# expansion_gpio.net
KiCad netlist of a schematic drawn in Altium Designer
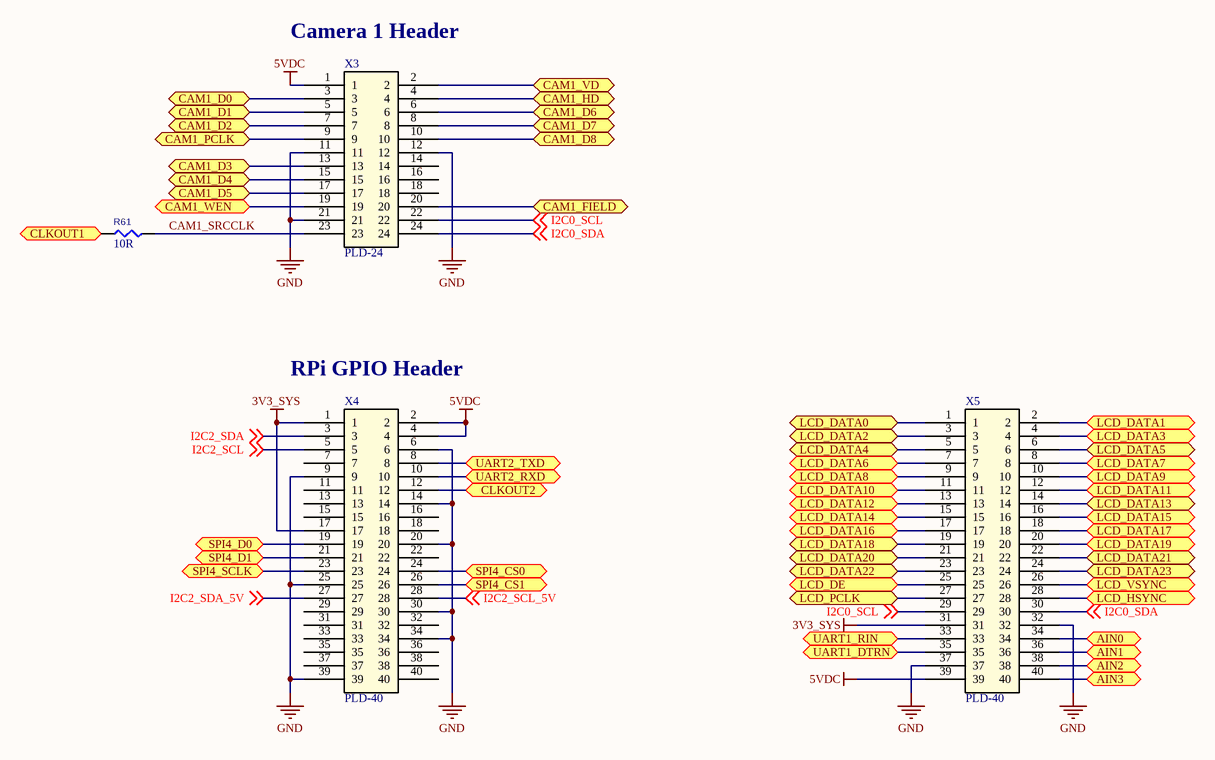
[diagram p0: expansion_gpio.SchDoc]

(export (version "E")
  (design (tool "Eeschema 10.0.6"))
  (components
    (comp (ref "R61")
      (value "10R")
      (footprint "RESC1608X55N")
      (description "R0603")
      (libsource (lib "spider") (part "R0603"))
    )
    (comp (ref "X3") (value "PLD-24") (footprint "PLD-24") (libsource (lib "spider") (part "HDR12x2")))
    (comp (ref "X4") (value "PLD-40") (footprint "PLD-40") (libsource (lib "spider") (part "HDR20x2")))
    (comp (ref "X5") (value "PLD-40") (footprint "PLD-40") (libsource (lib "spider") (part "HDR20x2")))
  )
  (nets
    (net (code "1") (name "/AIN0") (class "Default")
      (node (ref "X5") (pin "34") (pinfunction "34_34") (pintype "passive"))
    )
    (net (code "2") (name "/AIN1") (class "Default")
      (node (ref "X5") (pin "36") (pinfunction "36_36") (pintype "passive"))
    )
    (net (code "3") (name "/AIN2") (class "Default")
      (node (ref "X5") (pin "38") (pinfunction "38_38") (pintype "passive"))
    )
    (net (code "4") (name "/AIN3") (class "Default")
      (node (ref "X5") (pin "40") (pinfunction "40_40") (pintype "passive"))
    )
    (net (code "5") (name "/CAM1_D0") (class "Default")
      (node (ref "X3") (pin "3") (pinfunction "3_3") (pintype "passive"))
    )
    (net (code "6") (name "/CAM1_D1") (class "Default")
      (node (ref "X3") (pin "5") (pinfunction "5_5") (pintype "passive"))
    )
    (net (code "7") (name "/CAM1_D2") (class "Default")
      (node (ref "X3") (pin "7") (pinfunction "7_7") (pintype "passive"))
    )
    (net (code "8") (name "/CAM1_D3") (class "Default")
      (node (ref "X3") (pin "13") (pinfunction "13_13") (pintype "passive"))
    )
    (net (code "9") (name "/CAM1_D4") (class "Default")
      (node (ref "X3") (pin "15") (pinfunction "15_15") (pintype "passive"))
    )
    (net (code "10") (name "/CAM1_D5") (class "Default")
      (node (ref "X3") (pin "17") (pinfunction "17_17") (pintype "passive"))
    )
    (net (code "11") (name "/CAM1_D6") (class "Default")
      (node (ref "X3") (pin "6") (pinfunction "6_6") (pintype "passive"))
    )
    (net (code "12") (name "/CAM1_D7") (class "Default")
      (node (ref "X3") (pin "8") (pinfunction "8_8") (pintype "passive"))
    )
    (net (code "13") (name "/CAM1_D8") (class "Default")
      (node (ref "X3") (pin "10") (pinfunction "10_10") (pintype "passive"))
    )
    (net (code "14") (name "/CAM1_FIELD") (class "Default")
      (node (ref "X3") (pin "20") (pinfunction "20_20") (pintype "passive"))
    )
    (net (code "15") (name "/CAM1_HD") (class "Default")
      (node (ref "X3") (pin "4") (pinfunction "4_4") (pintype "passive"))
    )
    (net (code "16") (name "/CAM1_PCLK") (class "Default")
      (node (ref "X3") (pin "9") (pinfunction "9_9") (pintype "passive"))
    )
    (net (code "17") (name "/CAM1_SRCCLK") (class "Default")
      (node (ref "R61") (pin "2") (pinfunction "2_2") (pintype "passive"))
      (node (ref "X3") (pin "23") (pinfunction "23_23") (pintype "passive"))
    )
    (net (code "18") (name "/CAM1_VD") (class "Default")
      (node (ref "X3") (pin "2") (pinfunction "2_2") (pintype "passive"))
    )
    (net (code "19") (name "/CAM1_WEN") (class "Default")
      (node (ref "X3") (pin "19") (pinfunction "19_19") (pintype "passive"))
    )
    (net (code "20") (name "/CLKOUT1") (class "Default")
      (node (ref "R61") (pin "1") (pinfunction "1_1") (pintype "passive"))
    )
    (net (code "21") (name "/CLKOUT2") (class "Default")
      (node (ref "X4") (pin "12") (pinfunction "12_12") (pintype "passive"))
    )
    (net (code "22") (name "/LCD_DATA0") (class "Default")
      (node (ref "X5") (pin "1") (pinfunction "1_1") (pintype "passive"))
    )
    (net (code "23") (name "/LCD_DATA1") (class "Default")
      (node (ref "X5") (pin "2") (pinfunction "2_2") (pintype "passive"))
    )
    (net (code "24") (name "/LCD_DATA2") (class "Default")
      (node (ref "X5") (pin "3") (pinfunction "3_3") (pintype "passive"))
    )
    (net (code "25") (name "/LCD_DATA3") (class "Default")
      (node (ref "X5") (pin "4") (pinfunction "4_4") (pintype "passive"))
    )
    (net (code "26") (name "/LCD_DATA4") (class "Default")
      (node (ref "X5") (pin "5") (pinfunction "5_5") (pintype "passive"))
    )
    (net (code "27") (name "/LCD_DATA5") (class "Default")
      (node (ref "X5") (pin "6") (pinfunction "6_6") (pintype "passive"))
    )
    (net (code "28") (name "/LCD_DATA6") (class "Default")
      (node (ref "X5") (pin "7") (pinfunction "7_7") (pintype "passive"))
    )
    (net (code "29") (name "/LCD_DATA7") (class "Default")
      (node (ref "X5") (pin "8") (pinfunction "8_8") (pintype "passive"))
    )
    (net (code "30") (name "/LCD_DATA8") (class "Default")
      (node (ref "X5") (pin "9") (pinfunction "9_9") (pintype "passive"))
    )
    (net (code "31") (name "/LCD_DATA9") (class "Default")
      (node (ref "X5") (pin "10") (pinfunction "10_10") (pintype "passive"))
    )
    (net (code "32") (name "/LCD_DATA10") (class "Default")
      (node (ref "X5") (pin "11") (pinfunction "11_11") (pintype "passive"))
    )
    (net (code "33") (name "/LCD_DATA11") (class "Default")
      (node (ref "X5") (pin "12") (pinfunction "12_12") (pintype "passive"))
    )
    (net (code "34") (name "/LCD_DATA12") (class "Default")
      (node (ref "X5") (pin "13") (pinfunction "13_13") (pintype "passive"))
    )
    (net (code "35") (name "/LCD_DATA13") (class "Default")
      (node (ref "X5") (pin "14") (pinfunction "14_14") (pintype "passive"))
    )
    (net (code "36") (name "/LCD_DATA14") (class "Default")
      (node (ref "X5") (pin "15") (pinfunction "15_15") (pintype "passive"))
    )
    (net (code "37") (name "/LCD_DATA15") (class "Default")
      (node (ref "X5") (pin "16") (pinfunction "16_16") (pintype "passive"))
    )
    (net (code "38") (name "/LCD_DATA16") (class "Default")
      (node (ref "X5") (pin "17") (pinfunction "17_17") (pintype "passive"))
    )
    (net (code "39") (name "/LCD_DATA17") (class "Default")
      (node (ref "X5") (pin "18") (pinfunction "18_18") (pintype "passive"))
    )
    (net (code "40") (name "/LCD_DATA18") (class "Default")
      (node (ref "X5") (pin "19") (pinfunction "19_19") (pintype "passive"))
    )
    (net (code "41") (name "/LCD_DATA19") (class "Default")
      (node (ref "X5") (pin "20") (pinfunction "20_20") (pintype "passive"))
    )
    (net (code "42") (name "/LCD_DATA20") (class "Default")
      (node (ref "X5") (pin "21") (pinfunction "21_21") (pintype "passive"))
    )
    (net (code "43") (name "/LCD_DATA21") (class "Default")
      (node (ref "X5") (pin "22") (pinfunction "22_22") (pintype "passive"))
    )
    (net (code "44") (name "/LCD_DATA22") (class "Default")
      (node (ref "X5") (pin "23") (pinfunction "23_23") (pintype "passive"))
    )
    (net (code "45") (name "/LCD_DATA23") (class "Default")
      (node (ref "X5") (pin "24") (pinfunction "24_24") (pintype "passive"))
    )
    (net (code "46") (name "/LCD_DE") (class "Default")
      (node (ref "X5") (pin "25") (pinfunction "25_25") (pintype "passive"))
    )
    (net (code "47") (name "/LCD_HSYNC") (class "Default")
      (node (ref "X5") (pin "28") (pinfunction "28_28") (pintype "passive"))
    )
    (net (code "48") (name "/LCD_PCLK") (class "Default")
      (node (ref "X5") (pin "27") (pinfunction "27_27") (pintype "passive"))
    )
    (net (code "49") (name "/LCD_VSYNC") (class "Default")
      (node (ref "X5") (pin "26") (pinfunction "26_26") (pintype "passive"))
    )
    (net (code "50") (name "/SPI4_CS0") (class "Default")
      (node (ref "X4") (pin "24") (pinfunction "24_24") (pintype "passive"))
    )
    (net (code "51") (name "/SPI4_CS1") (class "Default")
      (node (ref "X4") (pin "26") (pinfunction "26_26") (pintype "passive"))
    )
    (net (code "52") (name "/SPI4_D0") (class "Default")
      (node (ref "X4") (pin "19") (pinfunction "19_19") (pintype "passive"))
    )
    (net (code "53") (name "/SPI4_D1") (class "Default")
      (node (ref "X4") (pin "21") (pinfunction "21_21") (pintype "passive"))
    )
    (net (code "54") (name "/SPI4_SCLK") (class "Default")
      (node (ref "X4") (pin "23") (pinfunction "23_23") (pintype "passive"))
    )
    (net (code "55") (name "/UART1_DTRN") (class "Default")
      (node (ref "X5") (pin "35") (pinfunction "35_35") (pintype "passive"))
    )
    (net (code "56") (name "/UART1_RIN") (class "Default")
      (node (ref "X5") (pin "33") (pinfunction "33_33") (pintype "passive"))
    )
    (net (code "57") (name "/UART2_RXD") (class "Default")
      (node (ref "X4") (pin "10") (pinfunction "10_10") (pintype "passive"))
    )
    (net (code "58") (name "/UART2_TXD") (class "Default")
      (node (ref "X4") (pin "8") (pinfunction "8_8") (pintype "passive"))
    )
    (net (code "59") (name "3V3_SYS") (class "Default")
      (node (ref "X4") (pin "1") (pinfunction "1_1") (pintype "passive"))
      (node (ref "X4") (pin "17") (pinfunction "17_17") (pintype "passive"))
      (node (ref "X5") (pin "31") (pinfunction "31_31") (pintype "passive"))
    )
    (net (code "60") (name "5VDC") (class "Default")
      (node (ref "X3") (pin "1") (pinfunction "1_1") (pintype "passive"))
      (node (ref "X4") (pin "2") (pinfunction "2_2") (pintype "passive"))
      (node (ref "X4") (pin "4") (pinfunction "4_4") (pintype "passive"))
      (node (ref "X5") (pin "39") (pinfunction "39_39") (pintype "passive"))
    )
    (net (code "61") (name "GND") (class "Default")
      (node (ref "X3") (pin "11") (pinfunction "11_11") (pintype "passive"))
      (node (ref "X3") (pin "12") (pinfunction "12_12") (pintype "passive"))
      (node (ref "X3") (pin "21") (pinfunction "21_21") (pintype "passive"))
      (node (ref "X4") (pin "14") (pinfunction "14_14") (pintype "passive"))
      (node (ref "X4") (pin "20") (pinfunction "20_20") (pintype "passive"))
      (node (ref "X4") (pin "25") (pinfunction "25_25") (pintype "passive"))
      (node (ref "X4") (pin "30") (pinfunction "30_30") (pintype "passive"))
      (node (ref "X4") (pin "34") (pinfunction "34_34") (pintype "passive"))
      (node (ref "X4") (pin "39") (pinfunction "39_39") (pintype "passive"))
      (node (ref "X4") (pin "6") (pinfunction "6_6") (pintype "passive"))
      (node (ref "X4") (pin "9") (pinfunction "9_9") (pintype "passive"))
      (node (ref "X5") (pin "32") (pinfunction "32_32") (pintype "passive"))
      (node (ref "X5") (pin "37") (pinfunction "37_37") (pintype "passive"))
    )
    (net (code "62") (name "I2C0_SCL") (class "Default")
      (node (ref "X3") (pin "22") (pinfunction "22_22") (pintype "passive"))
      (node (ref "X5") (pin "29") (pinfunction "29_29") (pintype "passive"))
    )
    (net (code "63") (name "I2C0_SDA") (class "Default")
      (node (ref "X3") (pin "24") (pinfunction "24_24") (pintype "passive"))
      (node (ref "X5") (pin "30") (pinfunction "30_30") (pintype "passive"))
    )
    (net (code "64") (name "I2C2_SCL") (class "Default")
      (node (ref "X4") (pin "5") (pinfunction "5_5") (pintype "passive"))
    )
    (net (code "65") (name "I2C2_SCL_5V") (class "Default")
      (node (ref "X4") (pin "28") (pinfunction "28_28") (pintype "passive"))
    )
    (net (code "66") (name "I2C2_SDA") (class "Default")
      (node (ref "X4") (pin "3") (pinfunction "3_3") (pintype "passive"))
    )
    (net (code "67") (name "I2C2_SDA_5V") (class "Default")
      (node (ref "X4") (pin "27") (pinfunction "27_27") (pintype "passive"))
    )
    (net (code "68") (name "unconnected-(X3-Pad14)") (class "Default")
      (node (ref "X3") (pin "14") (pinfunction "14_14") (pintype "passive"))
    )
    (net (code "69") (name "unconnected-(X3-Pad16)") (class "Default")
      (node (ref "X3") (pin "16") (pinfunction "16_16") (pintype "passive"))
    )
    (net (code "70") (name "unconnected-(X3-Pad18)") (class "Default")
      (node (ref "X3") (pin "18") (pinfunction "18_18") (pintype "passive"))
    )
    (net (code "71") (name "unconnected-(X4-Pad7)") (class "Default")
      (node (ref "X4") (pin "7") (pinfunction "7_7") (pintype "passive"))
    )
    (net (code "72") (name "unconnected-(X4-Pad11)") (class "Default")
      (node (ref "X4") (pin "11") (pinfunction "11_11") (pintype "passive"))
    )
    (net (code "73") (name "unconnected-(X4-Pad13)") (class "Default")
      (node (ref "X4") (pin "13") (pinfunction "13_13") (pintype "passive"))
    )
    (net (code "74") (name "unconnected-(X4-Pad15)") (class "Default")
      (node (ref "X4") (pin "15") (pinfunction "15_15") (pintype "passive"))
    )
    (net (code "75") (name "unconnected-(X4-Pad16)") (class "Default")
      (node (ref "X4") (pin "16") (pinfunction "16_16") (pintype "passive"))
    )
    (net (code "76") (name "unconnected-(X4-Pad18)") (class "Default")
      (node (ref "X4") (pin "18") (pinfunction "18_18") (pintype "passive"))
    )
    (net (code "77") (name "unconnected-(X4-Pad22)") (class "Default")
      (node (ref "X4") (pin "22") (pinfunction "22_22") (pintype "passive"))
    )
    (net (code "78") (name "unconnected-(X4-Pad29)") (class "Default")
      (node (ref "X4") (pin "29") (pinfunction "29_29") (pintype "passive"))
    )
    (net (code "79") (name "unconnected-(X4-Pad31)") (class "Default")
      (node (ref "X4") (pin "31") (pinfunction "31_31") (pintype "passive"))
    )
    (net (code "80") (name "unconnected-(X4-Pad32)") (class "Default")
      (node (ref "X4") (pin "32") (pinfunction "32_32") (pintype "passive"))
    )
    (net (code "81") (name "unconnected-(X4-Pad33)") (class "Default")
      (node (ref "X4") (pin "33") (pinfunction "33_33") (pintype "passive"))
    )
    (net (code "82") (name "unconnected-(X4-Pad35)") (class "Default")
      (node (ref "X4") (pin "35") (pinfunction "35_35") (pintype "passive"))
    )
    (net (code "83") (name "unconnected-(X4-Pad36)") (class "Default")
      (node (ref "X4") (pin "36") (pinfunction "36_36") (pintype "passive"))
    )
    (net (code "84") (name "unconnected-(X4-Pad37)") (class "Default")
      (node (ref "X4") (pin "37") (pinfunction "37_37") (pintype "passive"))
    )
    (net (code "85") (name "unconnected-(X4-Pad38)") (class "Default")
      (node (ref "X4") (pin "38") (pinfunction "38_38") (pintype "passive"))
    )
    (net (code "86") (name "unconnected-(X4-Pad40)") (class "Default")
      (node (ref "X4") (pin "40") (pinfunction "40_40") (pintype "passive"))
    )
  )
)
